# 3V3_to_5V.net
KiCad netlist of a schematic drawn in Altium Designer
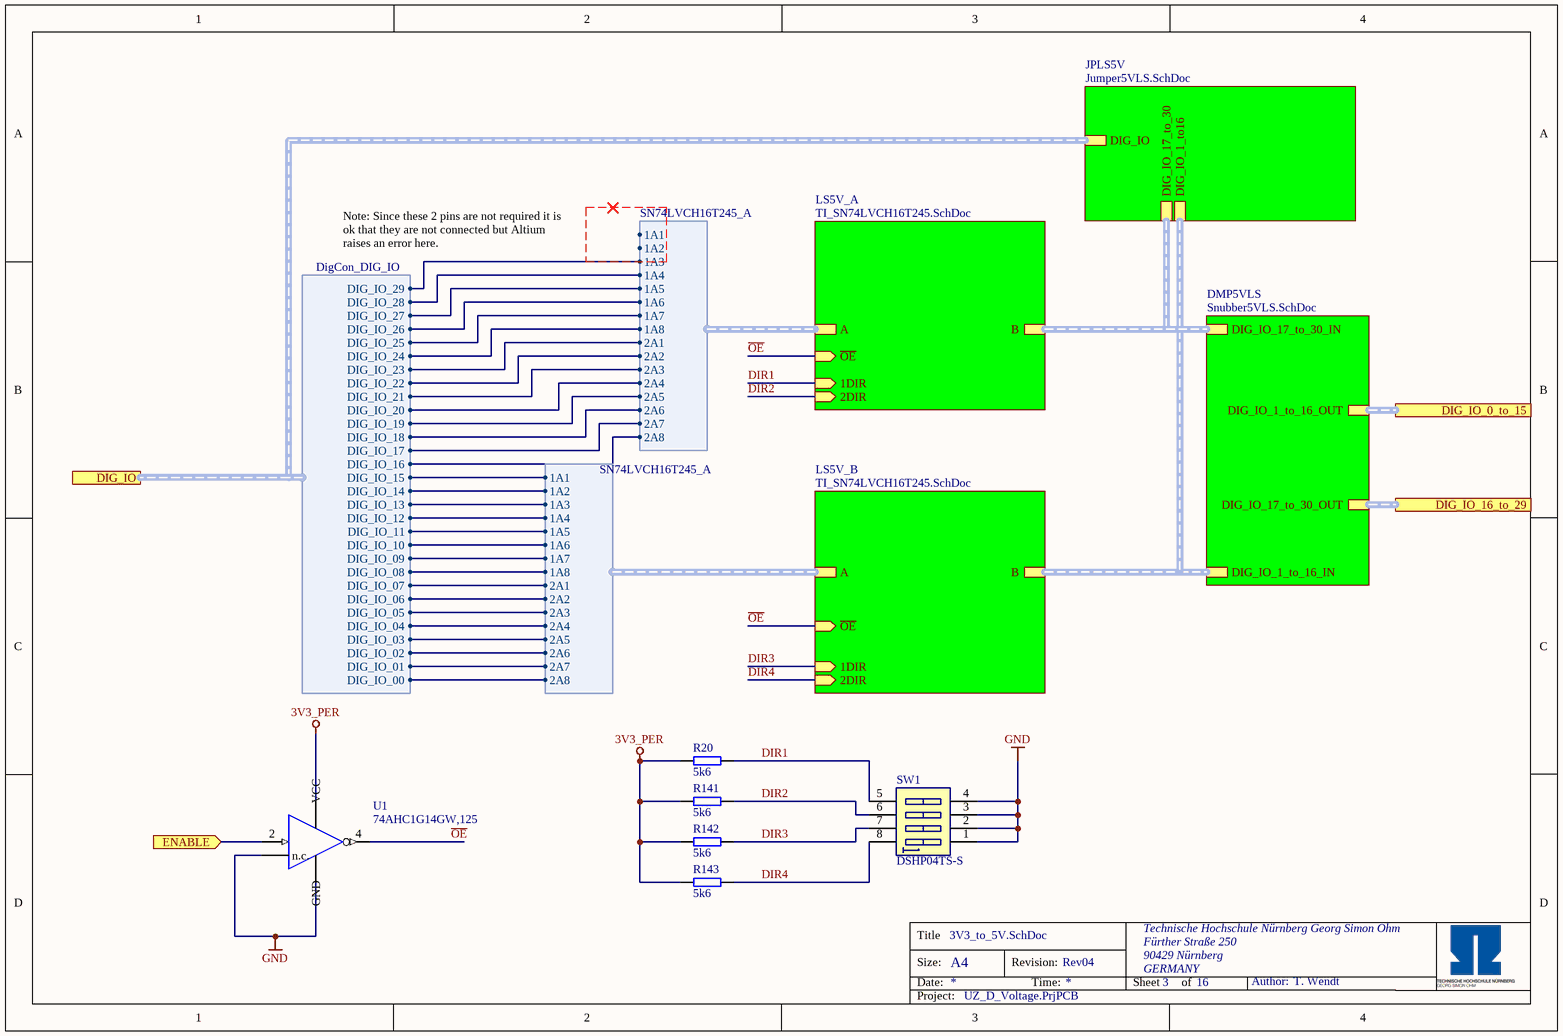
[diagram p0: 3V3_to_5V.SchDoc]

(export (version "E")
  (design (tool "Eeschema 10.0.6"))
  (components
    (comp (ref "R20")
      (value "5k6")
      (footprint "RES 0603_1608")
      (description "SMD resistor E24 series")
      (fields
        (field (name "MANUFACTURER PART NUMBER") "RK73B1JTTDD562J")
        (field (name "MANUFACTURER") "KOA Speer")
        (field (name "CREATED FROM") "MGremer")
      )
      (libsource (lib "user") (part "Resistor"))
    )
    (comp (ref "R141")
      (value "5k6")
      (footprint "RES 0603_1608")
      (description "SMD resistor E24 series")
      (fields
        (field (name "MANUFACTURER PART NUMBER") "RK73B1JTTDD562J")
        (field (name "MANUFACTURER") "KOA Speer")
        (field (name "CREATED FROM") "MGremer")
      )
      (libsource (lib "user") (part "Resistor"))
    )
    (comp (ref "R142")
      (value "5k6")
      (footprint "RES 0603_1608")
      (description "SMD resistor E24 series")
      (fields
        (field (name "MANUFACTURER PART NUMBER") "RK73B1JTTDD562J")
        (field (name "MANUFACTURER") "KOA Speer")
        (field (name "CREATED FROM") "MGremer")
      )
      (libsource (lib "user") (part "Resistor"))
    )
    (comp (ref "R143")
      (value "5k6")
      (footprint "RES 0603_1608")
      (description "SMD resistor E24 series")
      (fields
        (field (name "MANUFACTURER PART NUMBER") "RK73B1JTTDD562J")
        (field (name "MANUFACTURER") "KOA Speer")
        (field (name "CREATED FROM") "MGremer")
      )
      (libsource (lib "user") (part "Resistor"))
    )
    (comp (ref "SW1")
      (value "DSHP04TS-S")
      (footprint "416131160804")
      (description "04p, 1.27mm Pitch, Horizontal, HP Type, SMT, flat Actuator, black, with Tape, T&R")
      (fields
        (field (name "MANUFACTURER") "XKB Connectivity")
        (field (name "LCSC PART NUMBER") "C319050")
        (field (name "CREATED FROM") "T. Wendt")
      )
      (libsource (lib "user") (part "DIP-SW-4p"))
    )
    (comp (ref "U1")
      (value "74AHC1G14GW,125")
      (footprint "SOT353-1_N")
      (description "Inverting Schmitt trigger")
      (fields
        (field (name "MANUFACTURER") "Nexperia")
        (field (name "LCSC PART NUMBER") "C282410")
        (field (name "CREATED FROM") "MGremer")
      )
      (libsource (lib "user") (part "74AHCX1G14-5"))
    )
  )
  (nets
    (net (code "9") (name "/DIR1") (class "Default")
      (node (ref "R20") (pin "1") (pinfunction "1_1") (pintype "passive"))
      (node (ref "SW1") (pin "5") (pinfunction "5_5") (pintype "passive"))
    )
    (net (code "10") (name "/DIR2") (class "Default")
      (node (ref "R141") (pin "1") (pinfunction "1_1") (pintype "passive"))
      (node (ref "SW1") (pin "6") (pinfunction "6_6") (pintype "passive"))
    )
    (net (code "11") (name "/DIR3") (class "Default")
      (node (ref "R142") (pin "1") (pinfunction "1_1") (pintype "passive"))
      (node (ref "SW1") (pin "7") (pinfunction "7_7") (pintype "passive"))
    )
    (net (code "12") (name "/DIR4") (class "Default")
      (node (ref "R143") (pin "1") (pinfunction "1_1") (pintype "passive"))
      (node (ref "SW1") (pin "8") (pinfunction "8_8") (pintype "passive"))
    )
    (net (code "13") (name "/ENABLE") (class "Default")
      (node (ref "U1") (pin "2") (pinfunction "A_2") (pintype "input"))
    )
    (net (code "16") (name "/~{OE}") (class "Default")
      (node (ref "U1") (pin "4") (pinfunction "~{Y}_4") (pintype "output"))
    )
    (net (code "17") (name "3V3_PER") (class "Default")
      (node (ref "R141") (pin "2") (pinfunction "2_2") (pintype "passive"))
      (node (ref "R142") (pin "2") (pinfunction "2_2") (pintype "passive"))
      (node (ref "R143") (pin "2") (pinfunction "2_2") (pintype "passive"))
      (node (ref "R20") (pin "2") (pinfunction "2_2") (pintype "passive"))
      (node (ref "U1") (pin "5") (pinfunction "VCC_5") (pintype "power_in"))
    )
    (net (code "18") (name "GND") (class "Default")
      (node (ref "SW1") (pin "1") (pinfunction "1_1") (pintype "passive"))
      (node (ref "SW1") (pin "2") (pinfunction "2_2") (pintype "passive"))
      (node (ref "SW1") (pin "3") (pinfunction "3_3") (pintype "passive"))
      (node (ref "SW1") (pin "4") (pinfunction "4_4") (pintype "passive"))
      (node (ref "U1") (pin "1") (pinfunction "n.c._1") (pintype "passive"))
      (node (ref "U1") (pin "3") (pinfunction "GND_3") (pintype "power_in"))
    )
  )
)
